# TheSiS.net
KiCad netlist of a schematic drawn in EAGLE
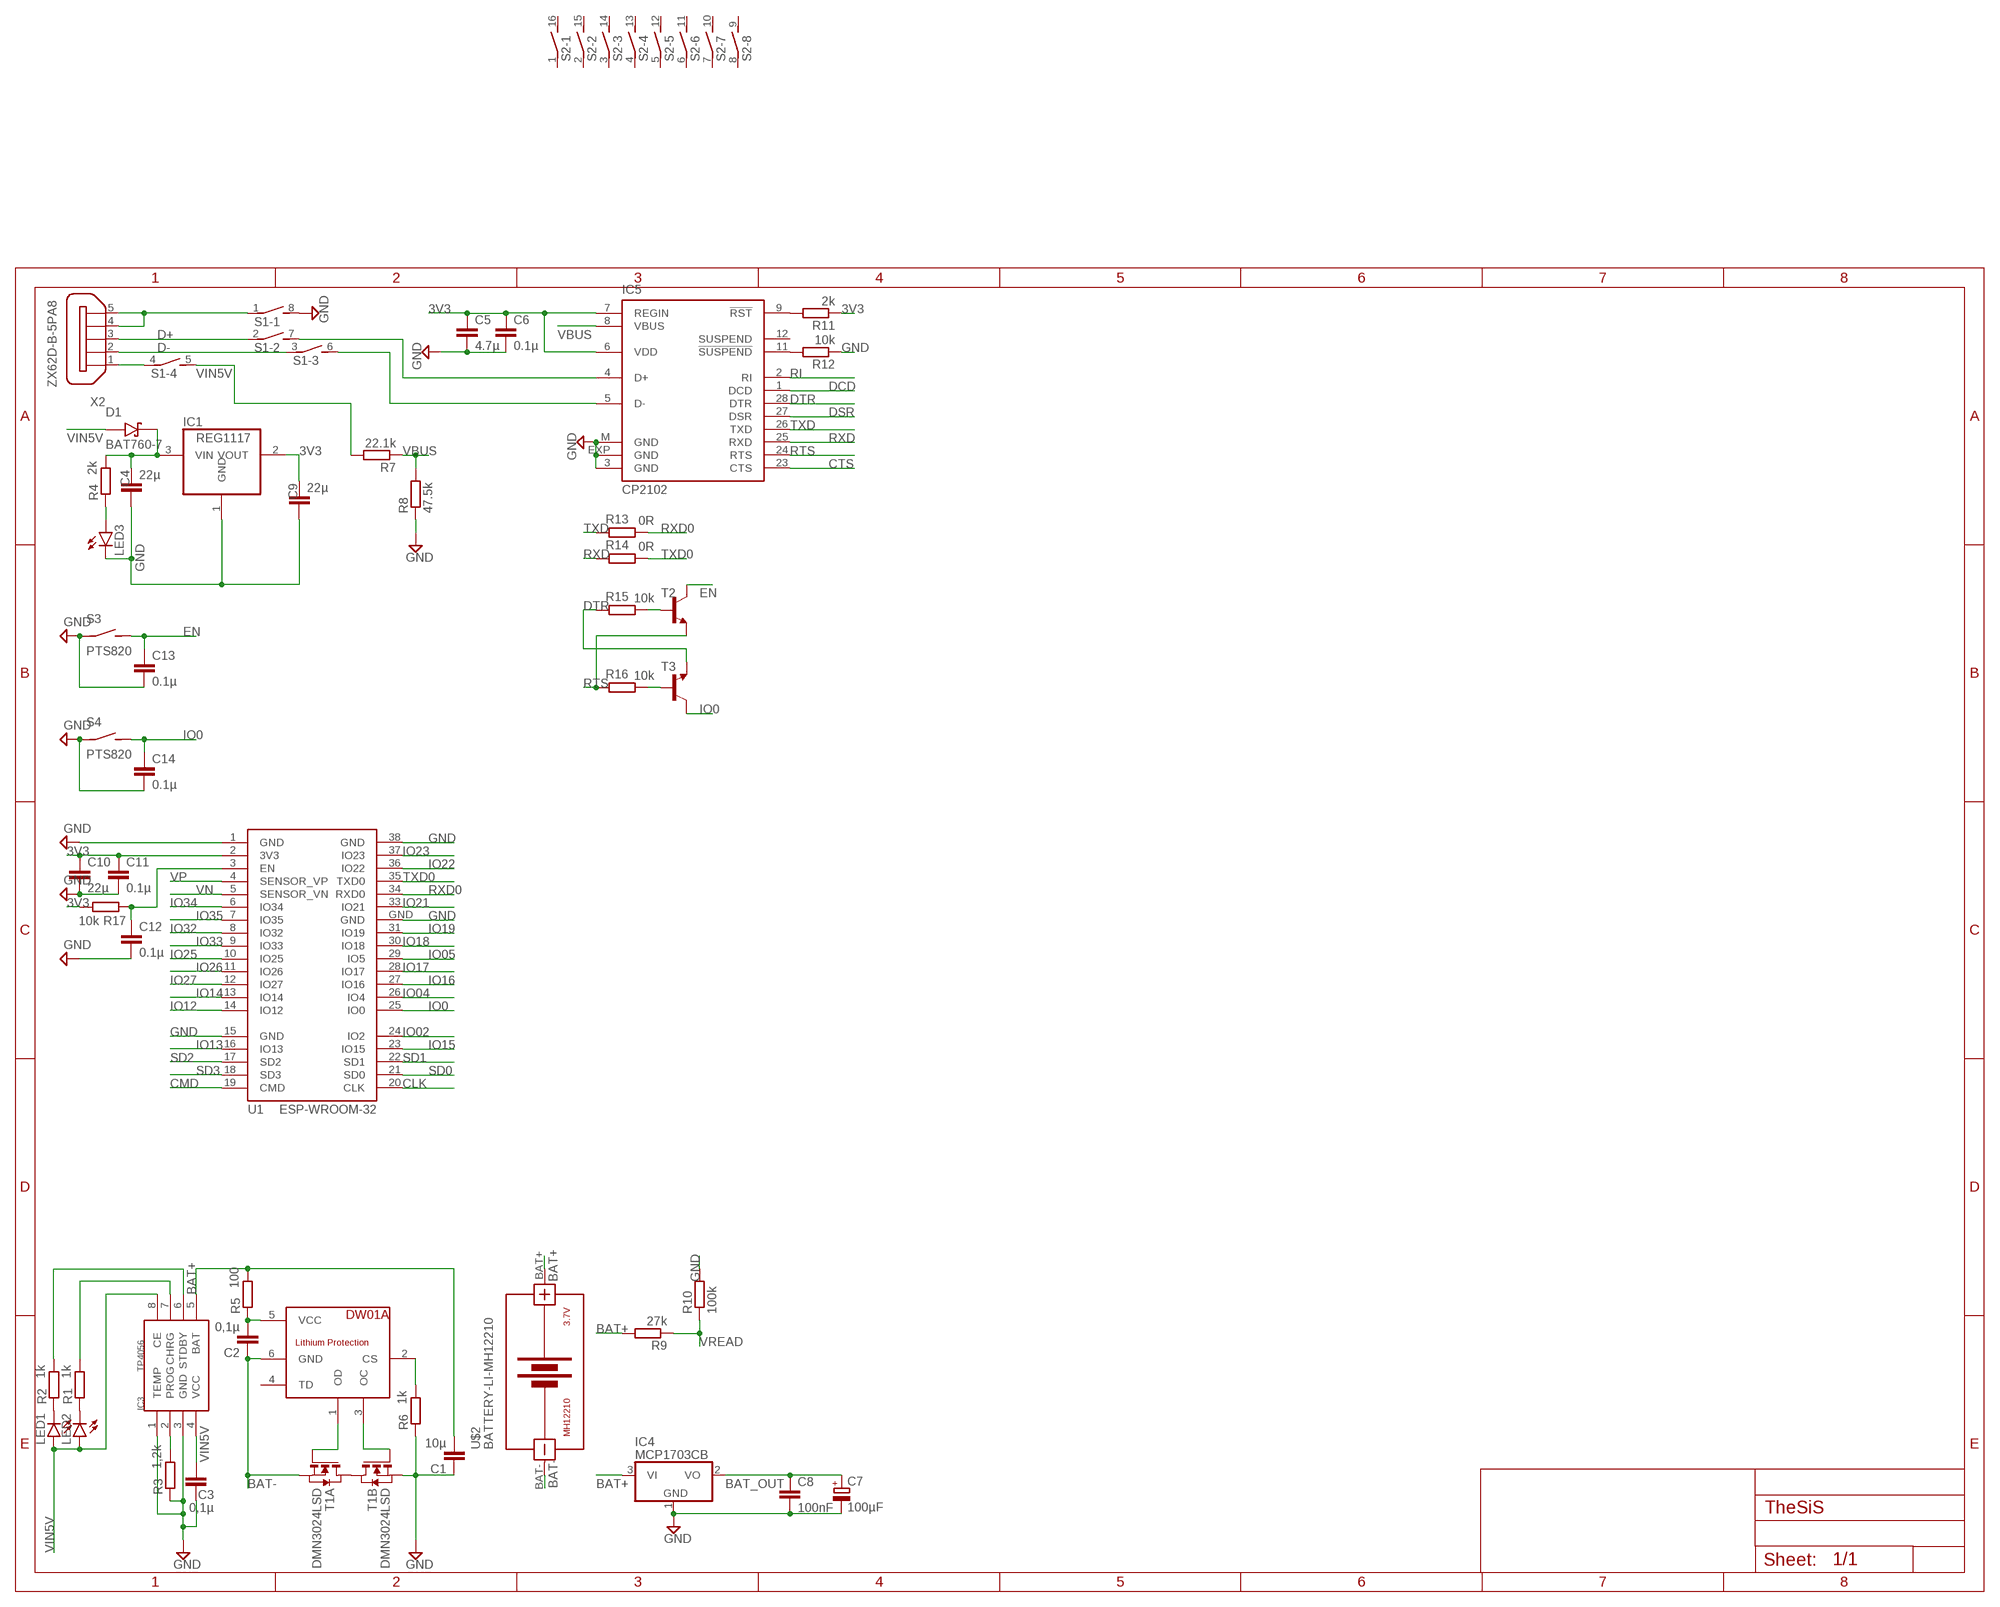
[diagram p0: schematic, sheet 1]

(export (version "E")
  (design (tool "Eeschema 10.0.6"))
  (components
    (comp (ref "C1")
      (value "10µ")
      (footprint "eagle-import:C0603K")
      (libsource (lib "eagle-import") (part "C-EUC0603K"))
    )
    (comp (ref "C2")
      (value "0,1µ")
      (footprint "eagle-import:C0805K")
      (libsource (lib "eagle-import") (part "C-EUC0805K"))
    )
    (comp (ref "C3")
      (value "0,1µ")
      (footprint "eagle-import:C0805K")
      (libsource (lib "eagle-import") (part "C-EUC0805K"))
    )
    (comp (ref "C4")
      (value "22µ")
      (footprint "eagle-import:C0805")
      (libsource (lib "eagle-import") (part "C-EUC0805"))
    )
    (comp (ref "C5")
      (value "4.7µ")
      (footprint "eagle-import:C0805")
      (libsource (lib "eagle-import") (part "C-EUC0805"))
    )
    (comp (ref "C6")
      (value "0.1µ")
      (footprint "eagle-import:C0805")
      (libsource (lib "eagle-import") (part "C-EUC0805"))
    )
    (comp (ref "C7")
      (value "100µF")
      (footprint "eagle-import:E2,5-6E")
      (libsource (lib "eagle-import") (part "CPOL-EUE2,5-6E"))
    )
    (comp (ref "C8")
      (value "100nF")
      (footprint "eagle-import:C0805")
      (libsource (lib "eagle-import") (part "C-EUC0805"))
    )
    (comp (ref "C9")
      (value "22µ")
      (footprint "eagle-import:C0805")
      (libsource (lib "eagle-import") (part "C-EUC0805"))
    )
    (comp (ref "C10")
      (value "22µ")
      (footprint "eagle-import:C0805")
      (libsource (lib "eagle-import") (part "C-EUC0805"))
    )
    (comp (ref "C11")
      (value "0.1µ")
      (footprint "eagle-import:C0805")
      (libsource (lib "eagle-import") (part "C-EUC0805"))
    )
    (comp (ref "C12")
      (value "0.1µ")
      (footprint "eagle-import:C0805")
      (libsource (lib "eagle-import") (part "C-EUC0805"))
    )
    (comp (ref "C13")
      (value "0.1µ")
      (footprint "eagle-import:C0805")
      (libsource (lib "eagle-import") (part "C-EUC0805"))
    )
    (comp (ref "C14")
      (value "0.1µ")
      (footprint "eagle-import:C0805")
      (libsource (lib "eagle-import") (part "C-EUC0805"))
    )
    (comp (ref "D1")
      (value "BAT760-7")
      (footprint "eagle-import:SOD2513X120N")
      (fields (field (name "MF") "Diodes Inc."))
      (libsource (lib "eagle-import") (part "BAT760-7"))
    )
    (comp (ref "IC1")
      (value "REG1117")
      (footprint "eagle-import:SOT223")
      (libsource (lib "eagle-import") (part "REG1117"))
    )
    (comp (ref "IC3")
      (value "TP4056")
      (footprint "eagle-import:SOP-8")
      (libsource (lib "eagle-import") (part "TP4056"))
    )
    (comp (ref "IC4")
      (value "MCP1703CB")
      (footprint "eagle-import:SOT23")
      (libsource (lib "eagle-import") (part "MCP1703CB"))
    )
    (comp (ref "IC5")
      (value "CP2102")
      (footprint "eagle-import:MLP28")
      (fields (field (name "MF") "FARNELL") (field (name "MPN") "CP2102-GM"))
      (libsource (lib "eagle-import") (part "CP2102"))
    )
    (comp (ref "LED1")
      (value "LEDCHIP-LED0805")
      (footprint "eagle-import:CHIP-LED0805")
      (libsource (lib "eagle-import") (part "LEDCHIP-LED0805"))
    )
    (comp (ref "LED2")
      (value "LEDCHIP-LED0805")
      (footprint "eagle-import:CHIP-LED0805")
      (libsource (lib "eagle-import") (part "LEDCHIP-LED0805"))
    )
    (comp (ref "LED3")
      (value "LEDCHIP-LED0805")
      (footprint "eagle-import:CHIP-LED0805")
      (libsource (lib "eagle-import") (part "LEDCHIP-LED0805"))
    )
    (comp (ref "R1")
      (value "1k")
      (footprint "eagle-import:R0603")
      (libsource (lib "eagle-import") (part "R-EU_R0603"))
    )
    (comp (ref "R2")
      (value "1k")
      (footprint "eagle-import:R0603")
      (libsource (lib "eagle-import") (part "R-EU_R0603"))
    )
    (comp (ref "R3")
      (value "1,2k")
      (footprint "eagle-import:R0603")
      (libsource (lib "eagle-import") (part "R-EU_R0603"))
    )
    (comp (ref "R4")
      (value "2k")
      (footprint "eagle-import:R0805")
      (libsource (lib "eagle-import") (part "R-EU_R0805"))
    )
    (comp (ref "R5")
      (value "100")
      (footprint "eagle-import:R0603")
      (libsource (lib "eagle-import") (part "R-EU_R0603"))
    )
    (comp (ref "R6")
      (value "1k")
      (footprint "eagle-import:R0603")
      (libsource (lib "eagle-import") (part "R-EU_R0603"))
    )
    (comp (ref "R7")
      (value "22.1k")
      (footprint "eagle-import:R0805")
      (libsource (lib "eagle-import") (part "R-EU_R0805"))
    )
    (comp (ref "R8")
      (value "47.5k")
      (footprint "eagle-import:R0805")
      (libsource (lib "eagle-import") (part "R-EU_R0805"))
    )
    (comp (ref "R9")
      (value "27k")
      (footprint "eagle-import:R0805")
      (libsource (lib "eagle-import") (part "R-EU_R0805"))
    )
    (comp (ref "R10")
      (value "100k")
      (footprint "eagle-import:R0805")
      (libsource (lib "eagle-import") (part "R-EU_R0805"))
    )
    (comp (ref "R11")
      (value "2k")
      (footprint "eagle-import:R0805")
      (libsource (lib "eagle-import") (part "R-EU_R0805"))
    )
    (comp (ref "R12")
      (value "10k")
      (footprint "eagle-import:R0805")
      (libsource (lib "eagle-import") (part "R-EU_R0805"))
    )
    (comp (ref "R13")
      (value "0R")
      (footprint "eagle-import:R0805")
      (libsource (lib "eagle-import") (part "R-EU_R0805"))
    )
    (comp (ref "R14")
      (value "0R")
      (footprint "eagle-import:R0805")
      (libsource (lib "eagle-import") (part "R-EU_R0805"))
    )
    (comp (ref "R15")
      (value "10k")
      (footprint "eagle-import:R0805")
      (libsource (lib "eagle-import") (part "R-EU_R0805"))
    )
    (comp (ref "R16")
      (value "10k")
      (footprint "eagle-import:R0805")
      (libsource (lib "eagle-import") (part "R-EU_R0805"))
    )
    (comp (ref "R17")
      (value "10k")
      (footprint "eagle-import:R0805")
      (libsource (lib "eagle-import") (part "R-EU_R0805"))
    )
    (comp (ref "S1")
      (value "DIP04S")
      (footprint "eagle-import:DIP04S")
      (libsource (lib "eagle-import") (part "DIP04S"))
    )
    (comp (ref "S2")
      (value "DIP08S")
      (footprint "eagle-import:DIP08S")
      (libsource (lib "eagle-import") (part "DIP08S"))
    )
    (comp (ref "S3")
      (value "PTS820")
      (footprint "eagle-import:PTS820")
      (libsource (lib "eagle-import") (part "PTS820"))
    )
    (comp (ref "S4")
      (value "PTS820")
      (footprint "eagle-import:PTS820")
      (libsource (lib "eagle-import") (part "PTS820"))
    )
    (comp (ref "T1")
      (value "DMN3024LSD")
      (footprint "eagle-import:TSSOP-8")
      (libsource (lib "eagle-import") (part "DMN3024LSD"))
    )
    (comp (ref "T2")
      (value "-NPN-SOT23-EBC")
      (footprint "eagle-import:SOT23-EBC")
      (libsource (lib "eagle-import") (part "-NPN-SOT23-EBC"))
    )
    (comp (ref "T3")
      (value "-NPN-SOT23-EBC")
      (footprint "eagle-import:SOT23-EBC")
      (libsource (lib "eagle-import") (part "-NPN-SOT23-EBC"))
    )
    (comp (ref "U$1")
      (value "DW01A")
      (footprint "eagle-import:SOT23-6")
      (libsource (lib "eagle-import") (part "DW01A"))
    )
    (comp (ref "U$2")
      (value "BATTERY-LI-MH12210")
      (footprint "eagle-import:BATTERY-LI-MH12210")
      (libsource (lib "eagle-import") (part "BATTERY-LI-MH12210"))
    )
    (comp (ref "U1")
      (value "ESP-WROOM-32")
      (footprint "eagle-import:ESP-WROOM-32")
      (libsource (lib "eagle-import") (part "ESP-WROOM-32"))
    )
    (comp (ref "X2")
      (value "ZX62D-B-5PA8")
      (footprint "eagle-import:ZX62D-B-5PA8")
      (fields (field (name "MF") "Hirose"))
      (libsource (lib "eagle-import") (part "ZX62D-B-5PA8"))
    )
  )
  (nets
    (net (code "1") (name "/3V3") (class "Default")
      (node (ref "C10") (pin "1") (pinfunction "1_1") (pintype "passive"))
      (node (ref "C11") (pin "1") (pinfunction "1_1") (pintype "passive"))
      (node (ref "C5") (pin "1") (pinfunction "1_1") (pintype "passive"))
      (node (ref "C6") (pin "1") (pinfunction "1_1") (pintype "passive"))
      (node (ref "C9") (pin "1") (pinfunction "1_1") (pintype "passive"))
      (node (ref "IC1") (pin "2") (pinfunction "VOUT_2") (pintype "output"))
      (node (ref "IC5") (pin "6") (pinfunction "VDD_6") (pintype "power_in"))
      (node (ref "IC5") (pin "7") (pinfunction "REGIN_7") (pintype "passive"))
      (node (ref "R11") (pin "1") (pinfunction "1_1") (pintype "passive"))
      (node (ref "R17") (pin "2") (pinfunction "2_2") (pintype "passive"))
      (node (ref "U1") (pin "2") (pinfunction "3V3_2") (pintype "power_in"))
    )
    (net (code "2") (name "/BAT+") (class "Default")
      (node (ref "C1") (pin "2") (pinfunction "2_2") (pintype "passive"))
      (node (ref "IC3") (pin "5") (pinfunction "BAT_5") (pintype "bidirectional"))
      (node (ref "IC4") (pin "3") (pinfunction "VI_3") (pintype "input"))
      (node (ref "R5") (pin "2") (pinfunction "2_2") (pintype "passive"))
      (node (ref "R9") (pin "2") (pinfunction "2_2") (pintype "passive"))
      (node (ref "U$2") (pin "BAT+") (pinfunction "BAT+_BAT+") (pintype "power_in"))
    )
    (net (code "3") (name "/BAT-") (class "Default")
      (node (ref "C2") (pin "1") (pinfunction "1_1") (pintype "passive"))
      (node (ref "T1") (pin "2") (pinfunction "S_2") (pintype "passive"))
      (node (ref "T1") (pin "3") (pinfunction "S_3") (pintype "passive"))
      (node (ref "U$1") (pin "6") (pinfunction "GND_6") (pintype "bidirectional"))
      (node (ref "U$2") (pin "BAT-") (pinfunction "BAT-_BAT-") (pintype "power_in"))
    )
    (net (code "4") (name "/BAT_OUT") (class "Default")
      (node (ref "C7") (pin "+") (pinfunction "+_+") (pintype "passive"))
      (node (ref "C8") (pin "1") (pinfunction "1_1") (pintype "passive"))
      (node (ref "IC4") (pin "2") (pinfunction "VO_2") (pintype "passive"))
    )
    (net (code "5") (name "/CLK") (class "Default")
      (node (ref "U1") (pin "20") (pinfunction "CLK_20") (pintype "bidirectional"))
    )
    (net (code "6") (name "/CMD") (class "Default")
      (node (ref "U1") (pin "19") (pinfunction "CMD_19") (pintype "bidirectional"))
    )
    (net (code "7") (name "/CTS") (class "Default")
      (node (ref "IC5") (pin "23") (pinfunction "CTS_23") (pintype "input"))
    )
    (net (code "8") (name "/D+") (class "Default")
      (node (ref "IC5") (pin "4") (pinfunction "D+_4") (pintype "bidirectional"))
      (node (ref "S1") (pin "7") (pinfunction "2_7") (pintype "passive"))
    )
    (net (code "9") (name "/D-") (class "Default")
      (node (ref "IC5") (pin "5") (pinfunction "D-_5") (pintype "bidirectional"))
      (node (ref "S1") (pin "6") (pinfunction "2_6") (pintype "passive"))
    )
    (net (code "10") (name "/DCD") (class "Default")
      (node (ref "IC5") (pin "1") (pinfunction "DCD_1") (pintype "input"))
    )
    (net (code "11") (name "/DSR") (class "Default")
      (node (ref "IC5") (pin "27") (pinfunction "DSR_27") (pintype "input"))
    )
    (net (code "12") (name "/DTR") (class "Default")
      (node (ref "IC5") (pin "28") (pinfunction "DTR_28") (pintype "output"))
      (node (ref "R15") (pin "2") (pinfunction "2_2") (pintype "passive"))
      (node (ref "T3") (pin "E") (pinfunction "E_E") (pintype "passive"))
    )
    (net (code "13") (name "/EN") (class "Default")
      (node (ref "C13") (pin "1") (pinfunction "1_1") (pintype "passive"))
      (node (ref "S3") (pin "2") (pinfunction "S_2") (pintype "passive"))
      (node (ref "T2") (pin "C") (pinfunction "C_C") (pintype "passive"))
    )
    (net (code "14") (name "/IO0") (class "Default")
      (node (ref "C14") (pin "1") (pinfunction "1_1") (pintype "passive"))
      (node (ref "S4") (pin "2") (pinfunction "S_2") (pintype "passive"))
      (node (ref "T3") (pin "C") (pinfunction "C_C") (pintype "passive"))
      (node (ref "U1") (pin "25") (pinfunction "IO0_25") (pintype "bidirectional"))
    )
    (net (code "15") (name "/IO02") (class "Default")
      (node (ref "U1") (pin "24") (pinfunction "IO2_24") (pintype "bidirectional"))
    )
    (net (code "16") (name "/IO04") (class "Default")
      (node (ref "U1") (pin "26") (pinfunction "IO4_26") (pintype "bidirectional"))
    )
    (net (code "17") (name "/IO05") (class "Default")
      (node (ref "U1") (pin "29") (pinfunction "IO5_29") (pintype "bidirectional"))
    )
    (net (code "18") (name "/IO12") (class "Default")
      (node (ref "U1") (pin "14") (pinfunction "IO12_14") (pintype "bidirectional"))
    )
    (net (code "19") (name "/IO13") (class "Default")
      (node (ref "U1") (pin "16") (pinfunction "IO13_16") (pintype "bidirectional"))
    )
    (net (code "20") (name "/IO14") (class "Default")
      (node (ref "U1") (pin "13") (pinfunction "IO14_13") (pintype "bidirectional"))
    )
    (net (code "21") (name "/IO15") (class "Default")
      (node (ref "U1") (pin "23") (pinfunction "IO15_23") (pintype "bidirectional"))
    )
    (net (code "22") (name "/IO16") (class "Default")
      (node (ref "U1") (pin "27") (pinfunction "IO16_27") (pintype "bidirectional"))
    )
    (net (code "23") (name "/IO17") (class "Default")
      (node (ref "U1") (pin "28") (pinfunction "IO17_28") (pintype "bidirectional"))
    )
    (net (code "24") (name "/IO18") (class "Default")
      (node (ref "U1") (pin "30") (pinfunction "IO18_30") (pintype "bidirectional"))
    )
    (net (code "25") (name "/IO19") (class "Default")
      (node (ref "U1") (pin "31") (pinfunction "IO19_31") (pintype "bidirectional"))
    )
    (net (code "26") (name "/IO21") (class "Default")
      (node (ref "U1") (pin "33") (pinfunction "IO21_33") (pintype "bidirectional"))
    )
    (net (code "27") (name "/IO22") (class "Default")
      (node (ref "U1") (pin "36") (pinfunction "IO22_36") (pintype "bidirectional"))
    )
    (net (code "28") (name "/IO23") (class "Default")
      (node (ref "U1") (pin "37") (pinfunction "IO23_37") (pintype "bidirectional"))
    )
    (net (code "29") (name "/IO25") (class "Default")
      (node (ref "U1") (pin "10") (pinfunction "IO25_10") (pintype "bidirectional"))
    )
    (net (code "30") (name "/IO26") (class "Default")
      (node (ref "U1") (pin "11") (pinfunction "IO26_11") (pintype "bidirectional"))
    )
    (net (code "31") (name "/IO27") (class "Default")
      (node (ref "U1") (pin "12") (pinfunction "IO27_12") (pintype "bidirectional"))
    )
    (net (code "32") (name "/IO32") (class "Default")
      (node (ref "U1") (pin "8") (pinfunction "IO32_8") (pintype "bidirectional"))
    )
    (net (code "33") (name "/IO33") (class "Default")
      (node (ref "U1") (pin "9") (pinfunction "IO33_9") (pintype "bidirectional"))
    )
    (net (code "34") (name "/IO34") (class "Default")
      (node (ref "U1") (pin "6") (pinfunction "IO34_6") (pintype "bidirectional"))
    )
    (net (code "35") (name "/IO35") (class "Default")
      (node (ref "U1") (pin "7") (pinfunction "IO35_7") (pintype "bidirectional"))
    )
    (net (code "36") (name "/RI") (class "Default")
      (node (ref "IC5") (pin "2") (pinfunction "RI_2") (pintype "input"))
    )
    (net (code "37") (name "/RTS") (class "Default")
      (node (ref "IC5") (pin "24") (pinfunction "RTS_24") (pintype "output"))
      (node (ref "R16") (pin "2") (pinfunction "2_2") (pintype "passive"))
      (node (ref "T2") (pin "E") (pinfunction "E_E") (pintype "passive"))
    )
    (net (code "38") (name "/RXD") (class "Default")
      (node (ref "IC5") (pin "25") (pinfunction "RXD_25") (pintype "input"))
      (node (ref "R14") (pin "2") (pinfunction "2_2") (pintype "passive"))
    )
    (net (code "39") (name "/RXD0") (class "Default")
      (node (ref "R13") (pin "1") (pinfunction "1_1") (pintype "passive"))
      (node (ref "U1") (pin "34") (pinfunction "RXD0_34") (pintype "bidirectional"))
    )
    (net (code "40") (name "/SD0") (class "Default")
      (node (ref "U1") (pin "21") (pinfunction "SD0_21") (pintype "bidirectional"))
    )
    (net (code "41") (name "/SD1") (class "Default")
      (node (ref "U1") (pin "22") (pinfunction "SD1_22") (pintype "bidirectional"))
    )
    (net (code "42") (name "/SD2") (class "Default")
      (node (ref "U1") (pin "17") (pinfunction "SD2_17") (pintype "bidirectional"))
    )
    (net (code "43") (name "/SD3") (class "Default")
      (node (ref "U1") (pin "18") (pinfunction "SD3_18") (pintype "bidirectional"))
    )
    (net (code "44") (name "/TXD") (class "Default")
      (node (ref "IC5") (pin "26") (pinfunction "TXD_26") (pintype "output"))
      (node (ref "R13") (pin "2") (pinfunction "2_2") (pintype "passive"))
    )
    (net (code "45") (name "/TXD0") (class "Default")
      (node (ref "R14") (pin "1") (pinfunction "1_1") (pintype "passive"))
      (node (ref "U1") (pin "35") (pinfunction "TXD0_35") (pintype "bidirectional"))
    )
    (net (code "46") (name "/VBUS") (class "Default")
      (node (ref "IC5") (pin "8") (pinfunction "VBUS_8") (pintype "input"))
      (node (ref "R7") (pin "1") (pinfunction "1_1") (pintype "passive"))
      (node (ref "R8") (pin "2") (pinfunction "2_2") (pintype "passive"))
    )
    (net (code "47") (name "/VIN5V") (class "Default")
      (node (ref "C3") (pin "2") (pinfunction "2_2") (pintype "passive"))
      (node (ref "C4") (pin "1") (pinfunction "1_1") (pintype "passive"))
      (node (ref "D1") (pin "A") (pinfunction "A_A") (pintype "passive"))
      (node (ref "D1") (pin "C") (pinfunction "K_C") (pintype "passive"))
      (node (ref "IC1") (pin "3") (pinfunction "VIN_3") (pintype "input"))
      (node (ref "IC3") (pin "4") (pinfunction "VCC_4") (pintype "bidirectional"))
      (node (ref "IC3") (pin "8") (pinfunction "CE_8") (pintype "bidirectional"))
      (node (ref "LED1") (pin "A") (pinfunction "A_A") (pintype "passive"))
      (node (ref "LED2") (pin "A") (pinfunction "A_A") (pintype "passive"))
      (node (ref "R4") (pin "2") (pinfunction "2_2") (pintype "passive"))
      (node (ref "R7") (pin "2") (pinfunction "2_2") (pintype "passive"))
      (node (ref "S1") (pin "5") (pinfunction "2_5") (pintype "passive"))
    )
    (net (code "48") (name "/VN") (class "Default")
      (node (ref "U1") (pin "5") (pinfunction "SENSOR_VN_5") (pintype "bidirectional"))
    )
    (net (code "49") (name "/VP") (class "Default")
      (node (ref "U1") (pin "4") (pinfunction "SENSOR_VP_4") (pintype "bidirectional"))
    )
    (net (code "50") (name "/VREAD") (class "Default")
      (node (ref "R10") (pin "1") (pinfunction "1_1") (pintype "passive"))
      (node (ref "R9") (pin "1") (pinfunction "1_1") (pintype "passive"))
    )
    (net (code "51") (name "GND") (class "Default")
      (node (ref "C1") (pin "1") (pinfunction "1_1") (pintype "passive"))
      (node (ref "C10") (pin "2") (pinfunction "2_2") (pintype "passive"))
      (node (ref "C11") (pin "2") (pinfunction "2_2") (pintype "passive"))
      (node (ref "C12") (pin "2") (pinfunction "2_2") (pintype "passive"))
      (node (ref "C13") (pin "2") (pinfunction "2_2") (pintype "passive"))
      (node (ref "C14") (pin "2") (pinfunction "2_2") (pintype "passive"))
      (node (ref "C3") (pin "1") (pinfunction "1_1") (pintype "passive"))
      (node (ref "C4") (pin "2") (pinfunction "2_2") (pintype "passive"))
      (node (ref "C5") (pin "2") (pinfunction "2_2") (pintype "passive"))
      (node (ref "C6") (pin "2") (pinfunction "2_2") (pintype "passive"))
      (node (ref "C7") (pin "-") (pinfunction "-_-") (pintype "passive"))
      (node (ref "C8") (pin "2") (pinfunction "2_2") (pintype "passive"))
      (node (ref "C9") (pin "2") (pinfunction "2_2") (pintype "passive"))
      (node (ref "IC1") (pin "1") (pinfunction "GND_1") (pintype "power_in"))
      (node (ref "IC3") (pin "1") (pinfunction "TEMP_1") (pintype "bidirectional"))
      (node (ref "IC3") (pin "3") (pinfunction "GND_3") (pintype "bidirectional"))
      (node (ref "IC4") (pin "1") (pinfunction "GND_1") (pintype "passive"))
      (node (ref "IC5") (pin "3") (pinfunction "GND_3") (pintype "power_in"))
      (node (ref "IC5") (pin "EXP") (pinfunction "GND_EXP") (pintype "power_in"))
      (node (ref "IC5") (pin "M") (pinfunction "GND_M") (pintype "power_in"))
      (node (ref "LED3") (pin "C") (pinfunction "C_C") (pintype "passive"))
      (node (ref "R10") (pin "2") (pinfunction "2_2") (pintype "passive"))
      (node (ref "R12") (pin "1") (pinfunction "1_1") (pintype "passive"))
      (node (ref "R3") (pin "1") (pinfunction "1_1") (pintype "passive"))
      (node (ref "R6") (pin "1") (pinfunction "1_1") (pintype "passive"))
      (node (ref "R8") (pin "1") (pinfunction "1_1") (pintype "passive"))
      (node (ref "S1") (pin "8") (pinfunction "2_8") (pintype "passive"))
      (node (ref "S3") (pin "1") (pinfunction "P_1") (pintype "passive"))
      (node (ref "S4") (pin "1") (pinfunction "P_1") (pintype "passive"))
      (node (ref "T1") (pin "6") (pinfunction "S_6") (pintype "passive"))
      (node (ref "T1") (pin "7") (pinfunction "S_7") (pintype "passive"))
      (node (ref "U1") (pin "1") (pinfunction "GND_1") (pintype "power_in"))
      (node (ref "U1") (pin "15") (pinfunction "GND_15") (pintype "power_in"))
      (node (ref "U1") (pin "38") (pinfunction "GND_38") (pintype "power_in"))
      (node (ref "U1") (pin "GND") (pinfunction "GND_GND") (pintype "power_in"))
    )
    (net (code "52") (name "Net-(IC3-CHRG)") (class "Default")
      (node (ref "IC3") (pin "7") (pinfunction "CHRG_7") (pintype "bidirectional"))
      (node (ref "R1") (pin "2") (pinfunction "2_2") (pintype "passive"))
    )
    (net (code "53") (name "Net-(IC3-PROG)") (class "Default")
      (node (ref "IC3") (pin "2") (pinfunction "PROG_2") (pintype "bidirectional"))
      (node (ref "R3") (pin "2") (pinfunction "2_2") (pintype "passive"))
    )
    (net (code "54") (name "Net-(IC3-STDBY)") (class "Default")
      (node (ref "IC3") (pin "6") (pinfunction "STDBY_6") (pintype "bidirectional"))
      (node (ref "R2") (pin "2") (pinfunction "2_2") (pintype "passive"))
    )
    (net (code "55") (name "Net-(IC5-~{RST})") (class "Default")
      (node (ref "IC5") (pin "9") (pinfunction "~{RST}_9") (pintype "bidirectional"))
      (node (ref "R11") (pin "2") (pinfunction "2_2") (pintype "passive"))
    )
    (net (code "56") (name "Net-(IC5-~{SUSPEND})") (class "Default")
      (node (ref "IC5") (pin "11") (pinfunction "~{SUSPEND}_11") (pintype "output"))
      (node (ref "R12") (pin "2") (pinfunction "2_2") (pintype "passive"))
    )
    (net (code "57") (name "Net-(LED1-PadC)") (class "Default")
      (node (ref "LED1") (pin "C") (pinfunction "C_C") (pintype "passive"))
      (node (ref "R2") (pin "1") (pinfunction "1_1") (pintype "passive"))
    )
    (net (code "58") (name "Net-(LED2-PadC)") (class "Default")
      (node (ref "LED2") (pin "C") (pinfunction "C_C") (pintype "passive"))
      (node (ref "R1") (pin "1") (pinfunction "1_1") (pintype "passive"))
    )
    (net (code "59") (name "Net-(LED3-PadA)") (class "Default")
      (node (ref "LED3") (pin "A") (pinfunction "A_A") (pintype "passive"))
      (node (ref "R4") (pin "1") (pinfunction "1_1") (pintype "passive"))
    )
    (net (code "60") (name "Net-(R15-Pad1)") (class "Default")
      (node (ref "R15") (pin "1") (pinfunction "1_1") (pintype "passive"))
      (node (ref "T2") (pin "B") (pinfunction "B_B") (pintype "passive"))
    )
    (net (code "61") (name "Net-(R16-Pad1)") (class "Default")
      (node (ref "R16") (pin "1") (pinfunction "1_1") (pintype "passive"))
      (node (ref "T3") (pin "B") (pinfunction "B_B") (pintype "passive"))
    )
    (net (code "62") (name "Net-(S1-Pad1)") (class "Default")
      (node (ref "S1") (pin "1") (pinfunction "1_1") (pintype "passive"))
      (node (ref "X2") (pin "4") (pinfunction "4_4") (pintype "passive"))
      (node (ref "X2") (pin "5") (pinfunction "5_5") (pintype "passive"))
    )
    (net (code "63") (name "Net-(S1B-1)") (class "Default")
      (node (ref "S1") (pin "2") (pinfunction "1_2") (pintype "passive"))
      (node (ref "X2") (pin "3") (pinfunction "3_3") (pintype "passive"))
    )
    (net (code "64") (name "Net-(S1C-1)") (class "Default")
      (node (ref "S1") (pin "3") (pinfunction "1_3") (pintype "passive"))
      (node (ref "X2") (pin "2") (pinfunction "2_2") (pintype "passive"))
    )
    (net (code "65") (name "Net-(S1D-1)") (class "Default")
      (node (ref "S1") (pin "4") (pinfunction "1_4") (pintype "passive"))
      (node (ref "X2") (pin "1") (pinfunction "1_1") (pintype "passive"))
    )
    (net (code "66") (name "Net-(T1A-D)") (class "Default")
      (node (ref "T1") (pin "1") (pinfunction "D_1") (pintype "passive"))
      (node (ref "T1") (pin "8") (pinfunction "D_8") (pintype "passive"))
    )
    (net (code "67") (name "Net-(T1A-G)") (class "Default")
      (node (ref "T1") (pin "4") (pinfunction "G_4") (pintype "passive"))
      (node (ref "U$1") (pin "1") (pinfunction "OD_1") (pintype "bidirectional"))
    )
    (net (code "68") (name "Net-(T1B-G)") (class "Default")
      (node (ref "T1") (pin "5") (pinfunction "G_5") (pintype "passive"))
      (node (ref "U$1") (pin "3") (pinfunction "OC_3") (pintype "bidirectional"))
    )
    (net (code "69") (name "Net-(U$1-CS)") (class "Default")
      (node (ref "R6") (pin "2") (pinfunction "2_2") (pintype "passive"))
      (node (ref "U$1") (pin "2") (pinfunction "CS_2") (pintype "bidirectional"))
    )
    (net (code "70") (name "Net-(U$1-VCC)") (class "Default")
      (node (ref "C2") (pin "2") (pinfunction "2_2") (pintype "passive"))
      (node (ref "R5") (pin "1") (pinfunction "1_1") (pintype "passive"))
      (node (ref "U$1") (pin "5") (pinfunction "VCC_5") (pintype "bidirectional"))
    )
    (net (code "71") (name "Net-(U1-EN)") (class "Default")
      (node (ref "C12") (pin "1") (pinfunction "1_1") (pintype "passive"))
      (node (ref "R17") (pin "1") (pinfunction "1_1") (pintype "passive"))
      (node (ref "U1") (pin "3") (pinfunction "EN_3") (pintype "input"))
    )
    (net (code "72") (name "unconnected-(IC5-SUSPEND-Pad12)") (class "Default")
      (node (ref "IC5") (pin "12") (pinfunction "SUSPEND_12") (pintype "output"))
    )
    (net (code "73") (name "unconnected-(S2-Pad1)") (class "Default")
      (node (ref "S2") (pin "1") (pinfunction "1_1") (pintype "passive"))
    )
    (net (code "74") (name "unconnected-(S2A-2-Pad16)") (class "Default")
      (node (ref "S2") (pin "16") (pinfunction "2_16") (pintype "passive"))
    )
    (net (code "75") (name "unconnected-(S2B-1-Pad2)") (class "Default")
      (node (ref "S2") (pin "2") (pinfunction "1_2") (pintype "passive"))
    )
    (net (code "76") (name "unconnected-(S2B-2-Pad15)") (class "Default")
      (node (ref "S2") (pin "15") (pinfunction "2_15") (pintype "passive"))
    )
    (net (code "77") (name "unconnected-(S2C-1-Pad3)") (class "Default")
      (node (ref "S2") (pin "3") (pinfunction "1_3") (pintype "passive"))
    )
    (net (code "78") (name "unconnected-(S2C-2-Pad14)") (class "Default")
      (node (ref "S2") (pin "14") (pinfunction "2_14") (pintype "passive"))
    )
    (net (code "79") (name "unconnected-(S2D-1-Pad4)") (class "Default")
      (node (ref "S2") (pin "4") (pinfunction "1_4") (pintype "passive"))
    )
    (net (code "80") (name "unconnected-(S2D-2-Pad13)") (class "Default")
      (node (ref "S2") (pin "13") (pinfunction "2_13") (pintype "passive"))
    )
    (net (code "81") (name "unconnected-(S2E-1-Pad5)") (class "Default")
      (node (ref "S2") (pin "5") (pinfunction "1_5") (pintype "passive"))
    )
    (net (code "82") (name "unconnected-(S2E-2-Pad12)") (class "Default")
      (node (ref "S2") (pin "12") (pinfunction "2_12") (pintype "passive"))
    )
    (net (code "83") (name "unconnected-(S2F-1-Pad6)") (class "Default")
      (node (ref "S2") (pin "6") (pinfunction "1_6") (pintype "passive"))
    )
    (net (code "84") (name "unconnected-(S2F-2-Pad11)") (class "Default")
      (node (ref "S2") (pin "11") (pinfunction "2_11") (pintype "passive"))
    )
    (net (code "85") (name "unconnected-(S2G-1-Pad7)") (class "Default")
      (node (ref "S2") (pin "7") (pinfunction "1_7") (pintype "passive"))
    )
    (net (code "86") (name "unconnected-(S2G-2-Pad10)") (class "Default")
      (node (ref "S2") (pin "10") (pinfunction "2_10") (pintype "passive"))
    )
    (net (code "87") (name "unconnected-(S2H-1-Pad8)") (class "Default")
      (node (ref "S2") (pin "8") (pinfunction "1_8") (pintype "passive"))
    )
    (net (code "88") (name "unconnected-(S2H-2-Pad9)") (class "Default")
      (node (ref "S2") (pin "9") (pinfunction "2_9") (pintype "passive"))
    )
    (net (code "89") (name "unconnected-(U$1-TD-Pad4)") (class "Default")
      (node (ref "U$1") (pin "4") (pinfunction "TD_4") (pintype "bidirectional"))
    )
  )
)
